# main.net
KiCad netlist of a schematic drawn in Altium Designer
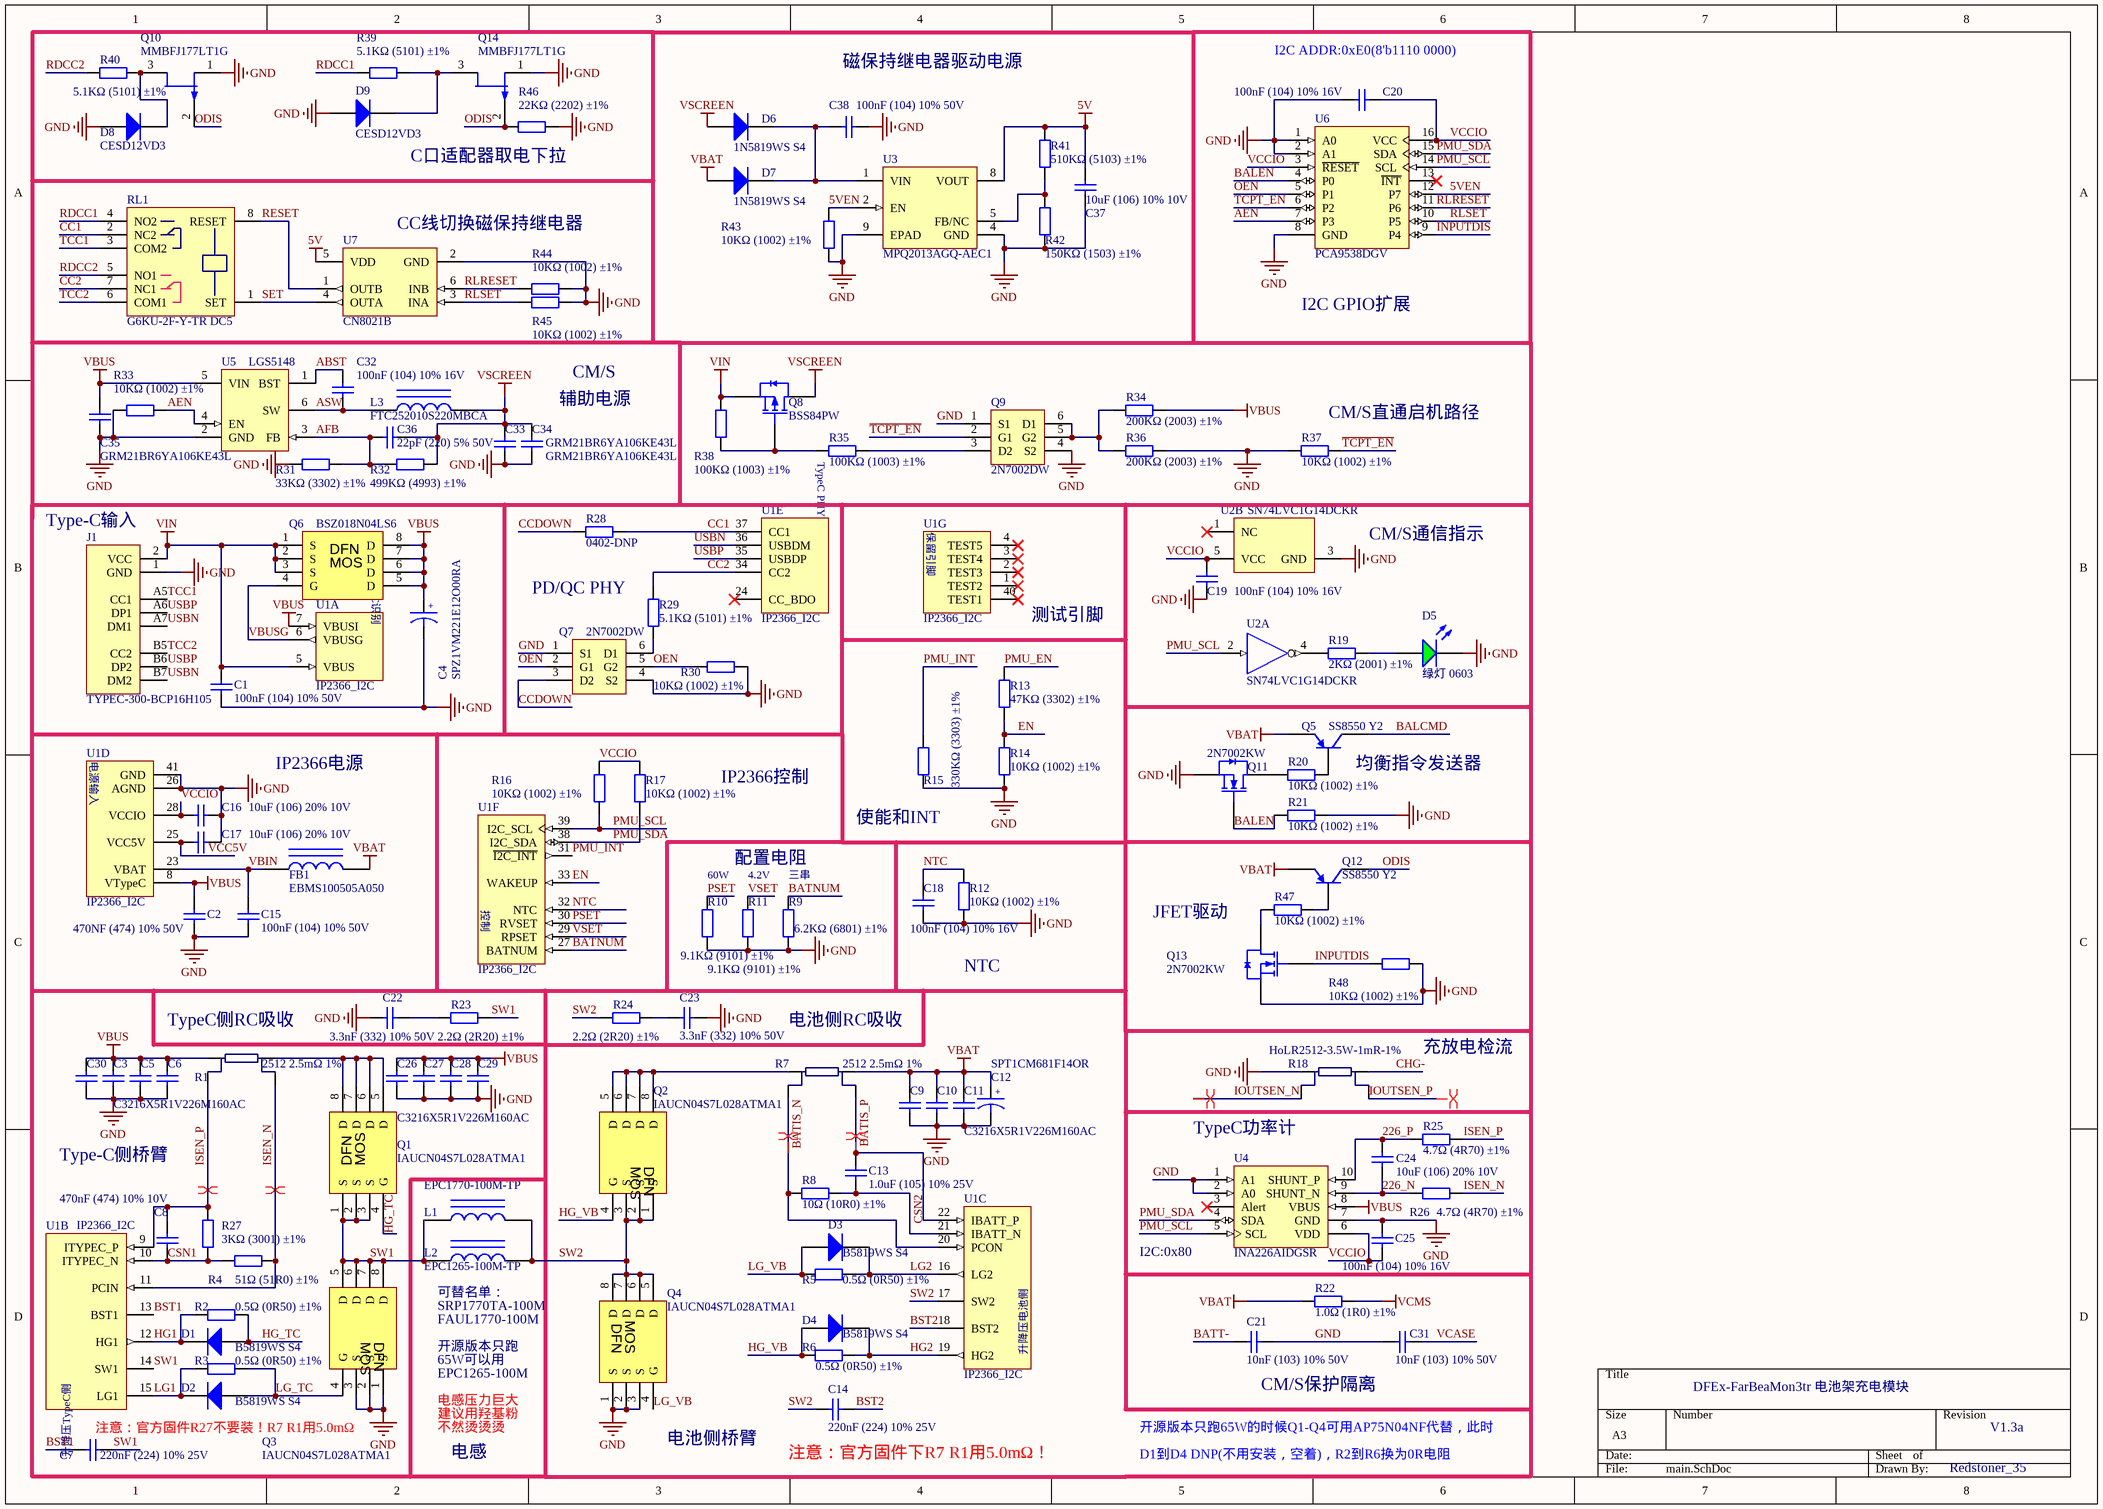
[diagram p0: main.SchDoc]

(export (version "E")
  (design (tool "Eeschema 10.0.6"))
  (components
    (comp (ref "C1")
      (value "100nF (104) 10% 50V")
      (footprint "0402_C")
      (description "贴片电容")
      (libsource (lib "Miscellaneous Devices LC") (part "0402 100nF (104) 10% 16V"))
    )
    (comp (ref "C2")
      (value "470NF (474) 10% 50V")
      (footprint "0402_C")
      (description "贴片电容")
      (libsource (lib "Miscellaneous Devices LC") (part "0402 1.0uF (105) 10% 25V"))
    )
    (comp (ref "C3")
      (value "C3216X5R1V226M160AC")
      (footprint "1206C")
      (description "1206尺寸TDK MLCC 35V 22uF")
      (fields (field (name "PUBLISHER") "Altium Limited"))
      (libsource (lib "山猫的集成库20190318") (part "Cap"))
    )
    (comp (ref "C4")
      (value "SPZ1VM221E12O00RA")
      (footprint "ElecCap_Hori")
      (description "直插固态电容，耐压35V容量220uF，尺寸6x11")
      (libsource (lib "山猫的集成库20190318") (part "CAP2"))
    )
    (comp (ref "C5")
      (value "C3216X5R1V226M160AC")
      (footprint "1206C")
      (description "1206尺寸TDK MLCC 35V 22uF")
      (fields (field (name "PUBLISHER") "Altium Limited"))
      (libsource (lib "山猫的集成库20190318") (part "Cap"))
    )
    (comp (ref "C6")
      (value "C3216X5R1V226M160AC")
      (footprint "1206C")
      (description "1206尺寸TDK MLCC 35V 22uF")
      (fields (field (name "PUBLISHER") "Altium Limited"))
      (libsource (lib "山猫的集成库20190318") (part "Cap"))
    )
    (comp (ref "C7")
      (value "220nF (224) 10% 25V")
      (footprint "0603_C")
      (description "贴片电容")
      (libsource (lib "Miscellaneous Devices LC") (part "0603 220nF (224) 10% 25V"))
    )
    (comp (ref "C8")
      (value "470nF (474) 10% 10V")
      (footprint "0402_C")
      (description "贴片电容")
      (libsource (lib "Miscellaneous Devices LC") (part "0402 470nF (474) 10% 10V"))
    )
    (comp (ref "C9")
      (value "C3216X5R1V226M160AC")
      (footprint "1206C")
      (description "1206尺寸TDK MLCC 35V 22uF")
      (fields (field (name "PUBLISHER") "Altium Limited"))
      (libsource (lib "山猫的集成库20190318") (part "Cap"))
    )
    (comp (ref "C10")
      (value "C3216X5R1V226M160AC")
      (footprint "1206C")
      (description "1206尺寸TDK MLCC 35V 22uF")
      (fields (field (name "PUBLISHER") "Altium Limited"))
      (libsource (lib "山猫的集成库20190318") (part "Cap"))
    )
    (comp (ref "C11")
      (value "C3216X5R1V226M160AC")
      (footprint "1206C")
      (description "1206尺寸TDK MLCC 35V 22uF")
      (fields (field (name "PUBLISHER") "Altium Limited"))
      (libsource (lib "山猫的集成库20190318") (part "Cap"))
    )
    (comp (ref "C12")
      (value "SPT1CM681F14OR")
      (footprint "ElecCap_Hori")
      (description "直插固态电容，耐压16V容量680uF，尺寸6x11")
      (libsource (lib "山猫的集成库20190318") (part "CAP2"))
    )
    (comp (ref "C13")
      (value "1.0uF (105) 10% 25V")
      (footprint "0402_C")
      (description "贴片电容")
      (libsource (lib "Miscellaneous Devices LC") (part "0402 1.0uF (105) 10% 25V"))
    )
    (comp (ref "C14")
      (value "220nF (224) 10% 25V")
      (footprint "0603_C")
      (description "贴片电容")
      (libsource (lib "Miscellaneous Devices LC") (part "0603 220nF (224) 10% 25V"))
    )
    (comp (ref "C15")
      (value "100nF (104) 10% 50V")
      (footprint "0402_C")
      (description "贴片电容")
      (libsource (lib "Miscellaneous Devices LC") (part "0402 100nF (104) 10% 16V"))
    )
    (comp (ref "C16")
      (value "10uF (106) 20% 10V")
      (footprint "0402_C")
      (description "贴片电容")
      (libsource (lib "Miscellaneous Devices LC") (part "0402 10uF (106) 20% 6.3V"))
    )
    (comp (ref "C17")
      (value "10uF (106) 20% 10V")
      (footprint "0402_C")
      (description "贴片电容")
      (libsource (lib "Miscellaneous Devices LC") (part "0402 10uF (106) 20% 6.3V"))
    )
    (comp (ref "C18")
      (value "100nF (104) 10% 16V")
      (footprint "0402_C")
      (description "贴片电容")
      (libsource (lib "Miscellaneous Devices LC") (part "0402 100nF (104) 10% 16V"))
    )
    (comp (ref "C19")
      (value "100nF (104) 10% 16V")
      (footprint "0402_C")
      (description "贴片电容")
      (libsource (lib "Miscellaneous Devices LC") (part "0402 100nF (104) 10% 16V"))
    )
    (comp (ref "C20")
      (value "100nF (104) 10% 16V")
      (footprint "0402_C")
      (description "贴片电容")
      (libsource (lib "Miscellaneous Devices LC") (part "0402 100nF (104) 10% 16V"))
    )
    (comp (ref "C21")
      (value "10nF (103) 10% 50V")
      (footprint "0402_C")
      (description "贴片电容")
      (libsource (lib "Miscellaneous Devices LC") (part "0402 10nF (103) 10% 50V"))
    )
    (comp (ref "C22")
      (value "3.3nF (332) 10% 50V")
      (footprint "0603_C")
      (description "贴片电容")
      (libsource (lib "Miscellaneous Devices LC") (part "0603 3.3nF (332) 10% 50V"))
    )
    (comp (ref "C23")
      (value "3.3nF (332) 10% 50V")
      (footprint "0603_C")
      (description "贴片电容")
      (libsource (lib "Miscellaneous Devices LC") (part "0603 3.3nF (332) 10% 50V"))
    )
    (comp (ref "C24")
      (value "10uF (106) 20% 10V")
      (footprint "0402_C")
      (description "贴片电容")
      (libsource (lib "Miscellaneous Devices LC") (part "0402 10uF (106) 20% 6.3V"))
    )
    (comp (ref "C25")
      (value "100nF (104) 10% 16V")
      (footprint "0402_C")
      (description "贴片电容")
      (libsource (lib "Miscellaneous Devices LC") (part "0402 100nF (104) 10% 16V"))
    )
    (comp (ref "C26")
      (value "C3216X5R1V226M160AC")
      (footprint "1206C")
      (description "1206尺寸TDK MLCC 35V 22uF")
      (fields (field (name "PUBLISHER") "Altium Limited"))
      (libsource (lib "山猫的集成库20190318") (part "Cap"))
    )
    (comp (ref "C27")
      (value "C3216X5R1V226M160AC")
      (footprint "1206C")
      (description "1206尺寸TDK MLCC 35V 22uF")
      (fields (field (name "PUBLISHER") "Altium Limited"))
      (libsource (lib "山猫的集成库20190318") (part "Cap"))
    )
    (comp (ref "C28")
      (value "C3216X5R1V226M160AC")
      (footprint "1206C")
      (description "1206尺寸TDK MLCC 35V 22uF")
      (fields (field (name "PUBLISHER") "Altium Limited"))
      (libsource (lib "山猫的集成库20190318") (part "Cap"))
    )
    (comp (ref "C29")
      (value "C3216X5R1V226M160AC")
      (footprint "1206C")
      (description "1206尺寸TDK MLCC 35V 22uF")
      (fields (field (name "PUBLISHER") "Altium Limited"))
      (libsource (lib "山猫的集成库20190318") (part "Cap"))
    )
    (comp (ref "C30")
      (value "C3216X5R1V226M160AC")
      (footprint "1206C")
      (description "1206尺寸TDK MLCC 35V 22uF")
      (fields (field (name "PUBLISHER") "Altium Limited"))
      (libsource (lib "山猫的集成库20190318") (part "Cap"))
    )
    (comp (ref "C31")
      (value "10nF (103) 10% 50V")
      (footprint "0402_C")
      (description "贴片电容")
      (libsource (lib "Miscellaneous Devices LC") (part "0402 10nF (103) 10% 50V"))
    )
    (comp (ref "C32")
      (value "100nF (104) 10% 16V")
      (footprint "0402_C")
      (description "贴片电容")
      (libsource (lib "Miscellaneous Devices LC") (part "0402 100nF (104) 10% 16V"))
    )
    (comp (ref "C33")
      (value "GRM21BR6YA106KE43L")
      (footprint "0805_C")
      (description "0805 10uF±10% 35V X5R贴片电容")
      (libsource (lib "Miscellaneous Devices LC") (part "0805 22uF (226) 20% 25V"))
    )
    (comp (ref "C34")
      (value "GRM21BR6YA106KE43L")
      (footprint "0805_C")
      (description "0805 10uF±10% 35V X5R贴片电容")
      (libsource (lib "Miscellaneous Devices LC") (part "0805 22uF (226) 20% 25V"))
    )
    (comp (ref "C35")
      (value "GRM21BR6YA106KE43L")
      (footprint "0805_C")
      (description "0805 10uF±10% 35V X5R贴片电容")
      (libsource (lib "Miscellaneous Devices LC") (part "0805 4.7uF (475) 10% 25V"))
    )
    (comp (ref "C36")
      (value "22pF (220) 5% 50V")
      (footprint "0402_C")
      (description "贴片电容")
      (libsource (lib "Miscellaneous Devices LC") (part "0402 22pF (220) 5% 50V"))
    )
    (comp (ref "C37")
      (value "10uF (106) 10% 10V")
      (footprint "0603_C")
      (description "贴片电容")
      (libsource (lib "Miscellaneous Devices LC") (part "0603 10uF (106) 10% 10V"))
    )
    (comp (ref "C38")
      (value "100nF (104) 10% 50V")
      (footprint "0402_C")
      (description "贴片电容")
      (libsource (lib "Miscellaneous Devices LC") (part "0402 100nF (104) 10% 16V"))
    )
    (comp (ref "D1")
      (value "B5819WS S4")
      (footprint "SOD-323")
      (description "二极管")
      (libsource (lib "Miscellaneous Devices LC") (part "SOD-323 1N4148WS T4"))
    )
    (comp (ref "D2")
      (value "B5819WS S4")
      (footprint "SOD-323")
      (description "二极管")
      (libsource (lib "Miscellaneous Devices LC") (part "SOD-323 1N4148WS T4"))
    )
    (comp (ref "D3")
      (value "B5819WS S4")
      (footprint "SOD-323")
      (description "二极管")
      (libsource (lib "Miscellaneous Devices LC") (part "SOD-323 1N4148WS T4"))
    )
    (comp (ref "D4")
      (value "B5819WS S4")
      (footprint "SOD-323")
      (description "二极管")
      (libsource (lib "Miscellaneous Devices LC") (part "SOD-323 1N4148WS T4"))
    )
    (comp (ref "D5")
      (value "绿灯 0603")
      (footprint "0603_LED_S1")
      (description "发光二极管")
      (libsource (lib "Miscellaneous Devices LC") (part "0603 绿灯"))
    )
    (comp (ref "D6")
      (value "1N5819WS S4")
      (footprint "SOD-323")
      (description "二极管")
      (libsource (lib "Miscellaneous Devices LC") (part "SOD-323 1N4148WS T4"))
    )
    (comp (ref "D7")
      (value "1N5819WS S4")
      (footprint "SOD-323")
      (description "二极管")
      (libsource (lib "Miscellaneous Devices LC") (part "SOD-323 1N4148WS T4"))
    )
    (comp (ref "D8")
      (value "CESD12VD3")
      (footprint "SOD-323")
      (description "TVS瞬态抑制二极管，12V击穿电压")
      (libsource (lib "Miscellaneous Devices LC") (part "SOD-323 1N4148WS T4"))
    )
    (comp (ref "D9")
      (value "CESD12VD3")
      (footprint "SOD-323")
      (description "TVS瞬态抑制二极管，12V击穿电压")
      (libsource (lib "Miscellaneous Devices LC") (part "SOD-323 1N4148WS T4"))
    )
    (comp (ref "FB1")
      (value "EBMS100505A050")
      (footprint "0402_L")
      (description "贴片磁珠 200mA 5R±25% 100MHz")
      (libsource (lib "Miscellaneous Devices LC") (part "0402 12nH  5%"))
    )
    (comp (ref "J1")
      (value "TYPEC-300-BCP16H105")
      (footprint "TYPE-C-SMD_TYPE-C16PIN")
      (description "立贴16Pin Type-C接口，总高度10.5mm")
      (libsource (lib "custom") (part "TYPEC-300-BCP16H105"))
    )
    (comp (ref "L1")
      (value "EPC1770-100M-TP")
      (footprint "IND1770-HD")
      (description "汇磁一体成型羟基粉电感，1770尺寸，10uH±20% 9.50mΩ DCR 25A饱和电流")
      (fields (field (name "PUBLISHER") "Altium Limited"))
      (libsource (lib "") (part "Inductor Iron_1"))
    )
    (comp (ref "L2")
      (value "EPC1265-100M-TP")
      (footprint "EPC1265-xxxM")
      (description "汇磁一体成型羟基粉电感，1265尺寸，10uH±20%")
      (fields (field (name "PUBLISHER") "Altium Limited"))
      (libsource (lib "") (part "Inductor Iron_1"))
    )
    (comp (ref "L3")
      (value "FTC252010S220MBCA")
      (footprint "SWPA252010S")
      (description "小型化一体成型T-CORE热压电感，22uH 2.5*2.0*1.0mm尺寸")
      (fields (field (name "PUBLISHER") "Altium Limited"))
      (libsource (lib "Miscellaneous Devices") (part "Inductor Iron"))
    )
    (comp (ref "Q1")
      (value "IAUCN04S7L028ATMA1")
      (footprint "SON/DFN5x6(MOS)")
      (description "40V, N-Ch, 2.80mΩ max, Automotive MOSFET, SSO8(5x6), OptiMOS™ 7")
      (libsource (lib "") (part "SON/DFN5x6 MOS_3"))
    )
    (comp (ref "Q2")
      (value "IAUCN04S7L028ATMA1")
      (footprint "SON/DFN5x6(MOS)")
      (description "40V, N-Ch, 2.80mΩ max, Automotive MOSFET, SSO8(5x6), OptiMOS™ 7")
      (libsource (lib "") (part "SON/DFN5x6 MOS_1"))
    )
    (comp (ref "Q3")
      (value "IAUCN04S7L028ATMA1")
      (footprint "SON/DFN5x6(MOS)")
      (description "40V, N-Ch, 2.80mΩ max, Automotive MOSFET, SSO8(5x6), OptiMOS™ 7")
      (libsource (lib "") (part "SON/DFN5x6 MOS_1"))
    )
    (comp (ref "Q4")
      (value "IAUCN04S7L028ATMA1")
      (footprint "SON/DFN5x6(MOS)")
      (description "40V, N-Ch, 2.80mΩ max, Automotive MOSFET, SSO8(5x6), OptiMOS™ 7")
      (libsource (lib "custom") (part "SON/DFN5x6 MOS"))
    )
    (comp (ref "Q5")
      (value "SS8550 Y2")
      (footprint "SOT-23(SOT-23-3)")
      (description "三极管")
      (libsource (lib "Miscellaneous Devices LC") (part "SOT-23 SS8550 Y2"))
    )
    (comp (ref "Q6")
      (value "BSZ018N04LS6")
      (footprint "DFN-8_L3.0-W3.0-P0.65-BL")
      (description "PDFN3x3 40V 60A 1.8mΩ N-Ch MOSFET")
      (libsource (lib "") (part "SON/DFN5x6 MOS_2"))
    )
    (comp (ref "Q7")
      (value "2N7002DW")
      (footprint "SC70-6")
      (description "Dual N-Channel MOSFET 60V340mA SOT-363")
      (libsource (lib "custom") (part "2N7002DW"))
    )
    (comp (ref "Q8")
      (value "BSS84PW")
      (footprint "SC70-3")
      (description "MOS(场效应管)")
      (libsource (lib "Miscellaneous Devices LC") (part "SI2301CDS-T1-GE3"))
    )
    (comp (ref "Q9")
      (value "2N7002DW")
      (footprint "SC70-6")
      (description "Dual N-Channel MOSFET 60V340mA SOT-363")
      (libsource (lib "custom") (part "2N7002DW"))
    )
    (comp (ref "Q10")
      (value "MMBFJ177LT1G")
      (footprint "SOT-23_N")
      (description "SOT-23-3耗尽型场效应管")
      (fields (field (name "PUBLISHER") "Altium Limited"))
      (libsource (lib "Miscellaneous Devices") (part "JFET-P"))
    )
    (comp (ref "Q11")
      (value "2N7002KW")
      (footprint "SC70-3")
      (description "单N沟道MOSFET(场效应管)")
      (libsource (lib "Miscellaneous Devices LC") (part "2N7002 7002"))
    )
    (comp (ref "Q12")
      (value "SS8550 Y2")
      (footprint "SC70-3")
      (description "PNP三极管，SOT-323 封装")
      (libsource (lib "Miscellaneous Devices LC") (part "SOT-23 SS8550 Y2"))
    )
    (comp (ref "Q13")
      (value "2N7002KW")
      (footprint "SC70-3")
      (description "单N沟道MOSFET(场效应管)")
      (libsource (lib "Miscellaneous Devices LC") (part "2N7002 7002"))
    )
    (comp (ref "Q14")
      (value "MMBFJ177LT1G")
      (footprint "SOT-23_N")
      (description "SOT-23-3耗尽型场效应管")
      (fields (field (name "PUBLISHER") "Altium Limited"))
      (libsource (lib "Miscellaneous Devices") (part "JFET-P"))
    )
    (comp (ref "R1")
      (value "2512 2.5mΩ 1%")
      (footprint "2512-Virtual4Wire")
      (description "2512尺寸高能电子束焊接合金检流电阻，2.5mΩ 3W 1%")
      (libsource (lib "custom") (part "shunt"))
    )
    (comp (ref "R2")
      (value "0.5Ω (0R50) ±1%")
      (footprint "0603_R")
      (description "贴片电阻")
      (libsource (lib "Miscellaneous Devices LC") (part "0603 0Ω (0R0) 1%"))
    )
    (comp (ref "R3")
      (value "0.5Ω (0R50) ±1%")
      (footprint "0603_R")
      (description "贴片电阻")
      (libsource (lib "Miscellaneous Devices LC") (part "0603 0Ω (0R0) 1%"))
    )
    (comp (ref "R4")
      (value "51Ω (51R0) ±1%")
      (footprint "0402_R")
      (description "贴片电阻")
      (libsource (lib "Miscellaneous Devices LC") (part "0402 51Ω (51R0) 1%"))
    )
    (comp (ref "R5")
      (value "0.5Ω (0R50) ±1%")
      (footprint "0603_R")
      (description "贴片电阻")
      (libsource (lib "Miscellaneous Devices LC") (part "0603 1.5KΩ (1501) 1%"))
    )
    (comp (ref "R6")
      (value "0.5Ω (0R50) ±1%")
      (footprint "0603_R")
      (description "贴片电阻")
      (libsource (lib "Miscellaneous Devices LC") (part "0603 1.5KΩ (1501) 1%"))
    )
    (comp (ref "R7")
      (value "2512 2.5mΩ 1%")
      (footprint "2512-Virtual4Wire")
      (description "2512尺寸高能电子束焊接合金检流电阻，2.5mΩ 3W 1%")
      (libsource (lib "custom") (part "shunt"))
    )
    (comp (ref "R8")
      (value "10Ω (10R0) ±1%")
      (footprint "0402_R")
      (description "贴片电阻")
      (libsource (lib "Miscellaneous Devices LC") (part "0402 10Ω (10R0) 1%"))
    )
    (comp (ref "R9")
      (value "6.2KΩ (6801) ±1%")
      (footprint "0402_R")
      (description "贴片电阻")
      (libsource (lib "Miscellaneous Devices LC") (part "0402 6.8KΩ (6801) 1%"))
    )
    (comp (ref "R10")
      (value "9.1KΩ (9101) ±1%")
      (footprint "0402_R")
      (description "贴片电阻")
      (libsource (lib "Miscellaneous Devices LC") (part "0402 6.8KΩ (6801) 1%"))
    )
    (comp (ref "R11")
      (value "9.1KΩ (9101) ±1%")
      (footprint "0402_R")
      (description "贴片电阻")
      (libsource (lib "Miscellaneous Devices LC") (part "0402 6.8KΩ (6801) 1%"))
    )
    (comp (ref "R12")
      (value "10KΩ (1002) ±1%")
      (footprint "0402_R")
      (description "贴片电阻")
      (libsource (lib "") (part "0402 10KΩ (1002) 1%_1"))
    )
    (comp (ref "R13")
      (value "47KΩ (3302) ±1%")
      (footprint "0603_R")
      (description "贴片电阻")
      (libsource (lib "Miscellaneous Devices LC") (part "0603 33KΩ (3302) 1%"))
    )
    (comp (ref "R14")
      (value "10KΩ (1002) ±1%")
      (footprint "0603_R")
      (description "贴片电阻")
      (libsource (lib "Miscellaneous Devices LC") (part "0603 10KΩ (1002) 1%"))
    )
    (comp (ref "R15")
      (value "330KΩ (3303) ±1%")
      (footprint "0603_R")
      (description "贴片电阻")
      (libsource (lib "Miscellaneous Devices LC") (part "0603 330KΩ (3303) 1%"))
    )
    (comp (ref "R16")
      (value "10KΩ (1002) ±1%")
      (footprint "0402_R")
      (description "贴片电阻")
      (libsource (lib "") (part "0402 10KΩ (1002) 1%_1"))
    )
    (comp (ref "R17")
      (value "10KΩ (1002) ±1%")
      (footprint "0402_R")
      (description "贴片电阻")
      (libsource (lib "") (part "0402 10KΩ (1002) 1%_1"))
    )
    (comp (ref "R18")
      (value "HoLR2512-3.5W-1mR-1%")
      (footprint "2512-Virtual4Wire")
      (description "2512尺寸低温飘合金检流电阻1.0mΩ 3.5W 1% TCR＜25PPM")
      (libsource (lib "custom") (part "shunt"))
    )
    (comp (ref "R19")
      (value "2KΩ (2001) ±1%")
      (footprint "0402_R")
      (description "贴片电阻")
      (libsource (lib "Miscellaneous Devices LC") (part "0402 2KΩ (2001) 1%"))
    )
    (comp (ref "R20")
      (value "10KΩ (1002) ±1%")
      (footprint "0402_R")
      (description "贴片电阻")
      (libsource (lib "Miscellaneous Devices LC") (part "0402 10KΩ (1002) 1%"))
    )
    (comp (ref "R21")
      (value "10KΩ (1002) ±1%")
      (footprint "0402_R")
      (description "贴片电阻")
      (libsource (lib "") (part "0402 10KΩ (1002) 1%_2"))
    )
    (comp (ref "R22")
      (value "1.0Ω (1R0) ±1%")
      (footprint "0805_R")
      (description "贴片电阻")
      (libsource (lib "Miscellaneous Devices LC") (part "0805 0Ω (0R0) 1%"))
    )
    (comp (ref "R23")
      (value "2.2Ω (2R20) ±1%")
      (footprint "0603_R")
      (description "贴片电阻")
      (libsource (lib "Miscellaneous Devices LC") (part "0603 2.2Ω (2R20) 1%"))
    )
    (comp (ref "R24")
      (value "2.2Ω (2R20) ±1%")
      (footprint "0603_R")
      (description "贴片电阻")
      (libsource (lib "") (part "0603 2.2Ω (2R20) 1%_1"))
    )
    (comp (ref "R25")
      (value "4.7Ω (4R70) ±1%")
      (footprint "0402_R")
      (description "贴片电阻")
      (libsource (lib "Miscellaneous Devices LC") (part "0402 4.7KΩ (4701) 1%"))
    )
    (comp (ref "R26")
      (value "4.7Ω (4R70) ±1%")
      (footprint "0402_R")
      (description "贴片电阻")
      (libsource (lib "Miscellaneous Devices LC") (part "0402 4.7KΩ (4701) 1%"))
    )
    (comp (ref "R27")
      (value "3KΩ (3001) ±1%")
      (footprint "0402_R")
      (description "贴片电阻")
      (libsource (lib "Miscellaneous Devices LC") (part "0402 3.3KΩ (3301) 1%"))
    )
    (comp (ref "R28")
      (value "0402-DNP")
      (footprint "0402_R")
      (description "测试焊点（特殊情况下焊贴片电阻）")
      (libsource (lib "") (part "0402 5.1KΩ (5101) 1%_1"))
    )
    (comp (ref "R29")
      (value "5.1KΩ (5101) ±1%")
      (footprint "0402_R")
      (description "贴片电阻")
      (libsource (lib "Miscellaneous Devices LC") (part "0402 5.1KΩ (5101) 1%"))
    )
    (comp (ref "R30")
      (value "10KΩ (1002) ±1%")
      (footprint "0402_R")
      (description "贴片电阻")
      (libsource (lib "Miscellaneous Devices LC") (part "0402 10KΩ (1002) 1%"))
    )
    (comp (ref "R31")
      (value "33KΩ (3302) ±1%")
      (footprint "0402_R")
      (description "贴片电阻")
      (libsource (lib "Miscellaneous Devices LC") (part "0402 300KΩ (3003) 1%"))
    )
    (comp (ref "R32")
      (value "499KΩ (4993) ±1%")
      (footprint "0402_R")
      (description "贴片电阻")
      (libsource (lib "") (part "0402 510KΩ (5103) 1%_1"))
    )
    (comp (ref "R33")
      (value "10KΩ (1002) ±1%")
      (footprint "0402_R")
      (description "贴片电阻")
      (libsource (lib "") (part "0402 10KΩ (1002) 1%_2"))
    )
    (comp (ref "R34")
      (value "200KΩ (2003) ±1%")
      (footprint "0402_R")
      (description "贴片电阻")
      (libsource (lib "Miscellaneous Devices LC") (part "0402 200KΩ (2003) 1%"))
    )
    (comp (ref "R35")
      (value "100KΩ (1003) ±1%")
      (footprint "0402_R")
      (description "贴片电阻")
      (libsource (lib "") (part "0402 100KΩ (1003) 1%_1"))
    )
    (comp (ref "R36")
      (value "200KΩ (2003) ±1%")
      (footprint "0402_R")
      (description "贴片电阻")
      (libsource (lib "Miscellaneous Devices LC") (part "0402 200KΩ (2003) 1%"))
    )
    (comp (ref "R37")
      (value "10KΩ (1002) ±1%")
      (footprint "0402_R")
      (description "贴片电阻")
      (libsource (lib "") (part "0402 10KΩ (1002) 1%_2"))
    )
    (comp (ref "R38")
      (value "100KΩ (1003) ±1%")
      (footprint "0402_R")
      (description "贴片电阻")
      (libsource (lib "Miscellaneous Devices LC") (part "0402 100KΩ (1003) 1%"))
    )
    (comp (ref "R39")
      (value "5.1KΩ (5101) ±1%")
      (footprint "0402_R")
      (description "贴片电阻")
      (libsource (lib "") (part "0402 5.1KΩ (5101) 1%_1"))
    )
    (comp (ref "R40")
      (value "5.1KΩ (5101) ±1%")
      (footprint "0402_R")
      (description "贴片电阻")
      (libsource (lib "") (part "0402 5.1KΩ (5101) 1%_1"))
    )
    (comp (ref "R41")
      (value "510KΩ (5103) ±1%")
      (footprint "0402_R")
      (description "贴片电阻")
      (libsource (lib "Miscellaneous Devices LC") (part "0402 510KΩ (5103) 1%"))
    )
    (comp (ref "R42")
      (value "150KΩ (1503) ±1%")
      (footprint "0402_R")
      (description "贴片电阻")
      (libsource (lib "Miscellaneous Devices LC") (part "0402 150KΩ (1503) 1%"))
    )
    (comp (ref "R43")
      (value "10KΩ (1002) ±1%")
      (footprint "0402_R")
      (description "贴片电阻")
      (libsource (lib "") (part "0402 10KΩ (1002) 1%_1"))
    )
    (comp (ref "R44")
      (value "10KΩ (1002) ±1%")
      (footprint "0402_R")
      (description "贴片电阻")
      (libsource (lib "") (part "0402 10KΩ (1002) 1%_2"))
    )
    (comp (ref "R45")
      (value "10KΩ (1002) ±1%")
      (footprint "0402_R")
      (description "贴片电阻")
      (libsource (lib "") (part "0402 10KΩ (1002) 1%_2"))
    )
    (comp (ref "R46")
      (value "22KΩ (2202) ±1%")
      (footprint "0402_R")
      (description "贴片电阻")
      (libsource (lib "Miscellaneous Devices LC") (part "0402 22KΩ (2202) 1%"))
    )
    (comp (ref "R47")
      (value "10KΩ (1002) ±1%")
      (footprint "0402_R")
      (description "贴片电阻")
      (libsource (lib "Miscellaneous Devices LC") (part "0402 10KΩ (1002) 1%"))
    )
    (comp (ref "R48")
      (value "10KΩ (1002) ±1%")
      (footprint "0402_R")
      (description "贴片电阻")
      (libsource (lib "Miscellaneous Devices LC") (part "0402 10KΩ (1002) 1%"))
    )
    (comp (ref "RL1")
      (value "G6KU-2F-Y-TR DC5")
      (footprint "RELAY-SMD_G6K-2F-Y")
      (description "欧姆龙双组触点磁保持贴片继电器")
      (libsource (lib "custom") (part "G6KU-2F-Y-TR DC5"))
    )
    (comp (ref "U1")
      (value "IP2366_I2C")
      (footprint "QFN40-IP2366")
      (description "支持多种快充协议，最高140W功率的充放电管理SoC")
      (libsource (lib "") (part "IP2366_I2C_1"))
    )
    (comp (ref "U2")
      (value "SN74LVC1G14DCKR")
      (footprint "DCK0005A_N")
      (description "Single Schmitt-Trigger Inverter, DCK0005A, LARGE T&R")
      (fields
        (field (name "GENERIC PART NUMBER") "SN74LVC1G14")
        (field (name "MANUFACTURER") "Texas Instruments")
      )
      (libsource (lib "TI_Logic_Little_Logic") (part "SN74LVC1G14DCKR"))
    )
    (comp (ref "U3")
      (value "MPQ2013AGQ-AEC1")
      (footprint "MPQ2013A-QFN8")
      (description "MPS 40V LDO with Enable pin QFN3x3 package")
      (libsource (lib "custom") (part "MPQ2013AGQ-xx-AEC1"))
    )
    (comp (ref "U4")
      (value "INA226AIDGSR")
      (footprint "MSOP-10")
      (description "具有警报功能的双向36V，16位，高精度I2C总线功率计")
      (libsource (lib "custom") (part "INA226AIDGSR"))
    )
    (comp (ref "U5")
      (value "LGS5148")
      (footprint "SOT95P245X110-6N")
      (description "48V输入，600mA同步降压转换器，SOT-23-6封装")
      (libsource (lib "custom") (part "LGS5148"))
    )
    (comp (ref "U6")
      (value "PCA9538DGV")
      (footprint "TVSOP-16_L3.6-W4.4-P0.40-LS6.4-BL")
      (description "具有中断输出、复位和配置寄存器的远程 8 位 I2C 和 SMBus 低功耗   I/O 扩展器")
      (libsource (lib "custom") (part "PCA9538DGV"))
    )
    (comp (ref "U7")
      (value "CN8021B")
      (footprint "SOT95P245X110-6N")
      (description "SOT23-6封装 双向磁保持继电器驱动IC 电压3.5-40V 450mA驱动能力")
      (libsource (lib "custom") (part "CN8023B"))
    )
  )
  (nets
    (net (code "1") (name "/5VEN") (class "Default")
      (node (ref "R43") (pin "2") (pinfunction "2_2") (pintype "passive"))
      (node (ref "U3") (pin "2") (pinfunction "EN_2") (pintype "input"))
      (node (ref "U6") (pin "12") (pinfunction "P7_12") (pintype "bidirectional"))
    )
    (net (code "2") (name "/226_N") (class "Default")
      (node (ref "C24") (pin "1") (pinfunction "1_1") (pintype "passive"))
      (node (ref "R26") (pin "1") (pinfunction "1_1") (pintype "passive"))
      (node (ref "U4") (pin "9") (pinfunction "SHUNT_N_9") (pintype "input"))
    )
    (net (code "3") (name "/226_P") (class "Default")
      (node (ref "C24") (pin "2") (pinfunction "2_2") (pintype "passive"))
      (node (ref "R25") (pin "1") (pinfunction "1_1") (pintype "passive"))
      (node (ref "U4") (pin "10") (pinfunction "SHUNT_P_10") (pintype "input"))
    )
    (net (code "4") (name "/ABST") (class "Default")
      (node (ref "C32") (pin "2") (pinfunction "2_2") (pintype "passive"))
      (node (ref "U5") (pin "1") (pinfunction "BST_1") (pintype "power_in"))
    )
    (net (code "5") (name "/AEN") (class "Default")
      (node (ref "R33") (pin "1") (pinfunction "1_1") (pintype "passive"))
      (node (ref "U5") (pin "4") (pinfunction "EN_4") (pintype "input"))
      (node (ref "U6") (pin "7") (pinfunction "P3_7") (pintype "bidirectional"))
    )
    (net (code "6") (name "/AFB") (class "Default")
      (node (ref "C36") (pin "1") (pinfunction "1_1") (pintype "passive"))
      (node (ref "R31") (pin "2") (pinfunction "2_2") (pintype "passive"))
      (node (ref "R32") (pin "1") (pinfunction "1_1") (pintype "passive"))
      (node (ref "U5") (pin "3") (pinfunction "FB_3") (pintype "input"))
    )
    (net (code "7") (name "/ASW") (class "Default")
      (node (ref "C32") (pin "1") (pinfunction "1_1") (pintype "passive"))
      (node (ref "L3") (pin "2") (pinfunction "2_2") (pintype "passive"))
      (node (ref "U5") (pin "6") (pinfunction "SW_6") (pintype "power_in"))
    )
    (net (code "8") (name "/BALCMD") (class "Default")
      (node (ref "Q5") (pin "3") (pinfunction "C_3") (pintype "passive"))
    )
    (net (code "9") (name "/BALEN") (class "Default")
      (node (ref "Q11") (pin "1") (pinfunction "G_1") (pintype "passive"))
      (node (ref "R21") (pin "2") (pinfunction "2_2") (pintype "passive"))
      (node (ref "U6") (pin "4") (pinfunction "P0_4") (pintype "bidirectional"))
    )
    (net (code "10") (name "/BATIS_N") (class "Default")
      (node (ref "R7") (pin "2") (pinfunction "CIN_2") (pintype "passive"))
      (node (ref "R8") (pin "1") (pinfunction "1_1") (pintype "passive"))
      (node (ref "U1") (pin "20") (pinfunction "PCON_20") (pintype "input"))
    )
    (net (code "11") (name "/BATIS_P") (class "Default")
      (node (ref "C13") (pin "2") (pinfunction "2_2") (pintype "passive"))
      (node (ref "R7") (pin "3") (pinfunction "CIN_3") (pintype "passive"))
      (node (ref "U1") (pin "22") (pinfunction "IBATT_P_22") (pintype "input"))
    )
    (net (code "12") (name "/BATNUM") (class "Default")
      (node (ref "R9") (pin "2") (pinfunction "2_2") (pintype "passive"))
      (node (ref "U1") (pin "27") (pinfunction "BATNUM_27") (pintype "input"))
    )
    (net (code "13") (name "/BATT-") (class "Default")
      (node (ref "C21") (pin "1") (pinfunction "1_1") (pintype "passive"))
    )
    (net (code "14") (name "/BST1") (class "Default")
      (node (ref "C7") (pin "1") (pinfunction "1_1") (pintype "passive"))
      (node (ref "U1") (pin "13") (pinfunction "BST1_13") (pintype "power_in"))
    )
    (net (code "15") (name "/BST2") (class "Default")
      (node (ref "C14") (pin "2") (pinfunction "2_2") (pintype "passive"))
      (node (ref "U1") (pin "18") (pinfunction "BST2_18") (pintype "power_in"))
    )
    (net (code "16") (name "/CC1") (class "Default")
      (node (ref "R28") (pin "2") (pinfunction "2_2") (pintype "passive"))
      (node (ref "RL1") (pin "2") (pinfunction "NC2_2") (pintype "passive"))
      (node (ref "U1") (pin "37") (pinfunction "CC1_37") (pintype "passive"))
    )
    (net (code "17") (name "/CC2") (class "Default")
      (node (ref "R29") (pin "2") (pinfunction "2_2") (pintype "passive"))
      (node (ref "RL1") (pin "7") (pinfunction "NC1_7") (pintype "passive"))
      (node (ref "U1") (pin "34") (pinfunction "CC2_34") (pintype "passive"))
    )
    (net (code "18") (name "/CCDOWN") (class "Default")
      (node (ref "Q7") (pin "3") (pinfunction "D2_3") (pintype "passive"))
      (node (ref "R28") (pin "1") (pinfunction "1_1") (pintype "passive"))
    )
    (net (code "19") (name "/CHG-") (class "Default")
      (node (ref "R18") (pin "0") (pinfunction "CIN_0") (pintype "passive"))
    )
    (net (code "20") (name "/CSN1") (class "Default")
      (node (ref "C8") (pin "1") (pinfunction "1_1") (pintype "passive"))
      (node (ref "R27") (pin "1") (pinfunction "1_1") (pintype "passive"))
      (node (ref "R4") (pin "1") (pinfunction "1_1") (pintype "passive"))
      (node (ref "U1") (pin "10") (pinfunction "ITYPEC_N_10") (pintype "input"))
    )
    (net (code "21") (name "/CSN2") (class "Default")
      (node (ref "C13") (pin "1") (pinfunction "1_1") (pintype "passive"))
      (node (ref "R8") (pin "2") (pinfunction "2_2") (pintype "passive"))
      (node (ref "U1") (pin "21") (pinfunction "IBATT_N_21") (pintype "input"))
    )
    (net (code "22") (name "/EN") (class "Default")
      (node (ref "R13") (pin "1") (pinfunction "1_1") (pintype "passive"))
      (node (ref "R14") (pin "2") (pinfunction "2_2") (pintype "passive"))
      (node (ref "U1") (pin "33") (pinfunction "WAKEUP_33") (pintype "input"))
    )
    (net (code "23") (name "/HG1") (class "Default")
      (node (ref "D1") (pin "2") (pinfunction "K_2") (pintype "passive"))
      (node (ref "R2") (pin "1") (pinfunction "1_1") (pintype "passive"))
      (node (ref "U1") (pin "12") (pinfunction "HG1_12") (pintype "output"))
    )
    (net (code "24") (name "/HG2") (class "Default")
      (node (ref "D4") (pin "2") (pinfunction "K_2") (pintype "passive"))
      (node (ref "R6") (pin "2") (pinfunction "2_2") (pintype "passive"))
      (node (ref "U1") (pin "19") (pinfunction "HG2_19") (pintype "output"))
    )
    (net (code "25") (name "/HG_TC") (class "Default")
      (node (ref "D1") (pin "1") (pinfunction "A_1") (pintype "passive"))
      (node (ref "Q1") (pin "4") (pinfunction "G_4") (pintype "passive"))
      (node (ref "R2") (pin "2") (pinfunction "2_2") (pintype "passive"))
    )
    (net (code "26") (name "/HG_VB") (class "Default")
      (node (ref "D4") (pin "1") (pinfunction "A_1") (pintype "passive"))
      (node (ref "Q2") (pin "4") (pinfunction "G_4") (pintype "passive"))
      (node (ref "R6") (pin "1") (pinfunction "1_1") (pintype "passive"))
    )
    (net (code "27") (name "/INPUTDIS") (class "Default")
      (node (ref "Q13") (pin "1") (pinfunction "G_1") (pintype "passive"))
      (node (ref "R48") (pin "1") (pinfunction "1_1") (pintype "passive"))
      (node (ref "U6") (pin "9") (pinfunction "P4_9") (pintype "bidirectional"))
    )
    (net (code "28") (name "/IOUTSEN_N") (class "Default")
      (node (ref "R18") (pin "3") (pinfunction "CIN_3") (pintype "passive"))
    )
    (net (code "29") (name "/IOUTSEN_P") (class "Default")
      (node (ref "R18") (pin "2") (pinfunction "CIN_2") (pintype "passive"))
    )
    (net (code "30") (name "/ISEN_N") (class "Default")
      (node (ref "R1") (pin "3") (pinfunction "CIN_3") (pintype "passive"))
      (node (ref "R26") (pin "2") (pinfunction "2_2") (pintype "passive"))
      (node (ref "R4") (pin "2") (pinfunction "2_2") (pintype "passive"))
      (node (ref "U1") (pin "11") (pinfunction "PCIN_11") (pintype "input"))
    )
    (net (code "31") (name "/ISEN_P") (class "Default")
      (node (ref "C8") (pin "2") (pinfunction "2_2") (pintype "passive"))
      (node (ref "R1") (pin "2") (pinfunction "CIN_2") (pintype "passive"))
      (node (ref "R25") (pin "2") (pinfunction "2_2") (pintype "passive"))
      (node (ref "R27") (pin "2") (pinfunction "2_2") (pintype "passive"))
      (node (ref "U1") (pin "9") (pinfunction "ITYPEC_P_9") (pintype "input"))
    )
    (net (code "32") (name "/LG1") (class "Default")
      (node (ref "D2") (pin "2") (pinfunction "K_2") (pintype "passive"))
      (node (ref "R3") (pin "1") (pinfunction "1_1") (pintype "passive"))
      (node (ref "U1") (pin "15") (pinfunction "LG1_15") (pintype "power_in"))
    )
    (net (code "33") (name "/LG2") (class "Default")
      (node (ref "D3") (pin "2") (pinfunction "K_2") (pintype "passive"))
      (node (ref "R5") (pin "2") (pinfunction "2_2") (pintype "passive"))
      (node (ref "U1") (pin "16") (pinfunction "LG2_16") (pintype "output"))
    )
    (net (code "34") (name "/LG_TC") (class "Default")
      (node (ref "D2") (pin "1") (pinfunction "A_1") (pintype "passive"))
      (node (ref "Q3") (pin "4") (pinfunction "G_4") (pintype "passive"))
      (node (ref "R3") (pin "2") (pinfunction "2_2") (pintype "passive"))
    )
    (net (code "35") (name "/LG_VB") (class "Default")
      (node (ref "D3") (pin "1") (pinfunction "A_1") (pintype "passive"))
      (node (ref "Q4") (pin "4") (pinfunction "G_4") (pintype "passive"))
      (node (ref "R5") (pin "1") (pinfunction "1_1") (pintype "passive"))
    )
    (net (code "36") (name "/NTC") (class "Default")
      (node (ref "C18") (pin "2") (pinfunction "2_2") (pintype "passive"))
      (node (ref "R12") (pin "2") (pinfunction "2_2") (pintype "passive"))
      (node (ref "U1") (pin "32") (pinfunction "NTC_32") (pintype "input"))
    )
    (net (code "37") (name "/ODIS") (class "Default")
      (node (ref "Q10") (pin "2") (pinfunction "G_2") (pintype "passive"))
      (node (ref "Q12") (pin "3") (pinfunction "C_3") (pintype "passive"))
      (node (ref "Q14") (pin "2") (pinfunction "G_2") (pintype "passive"))
      (node (ref "R46") (pin "1") (pinfunction "1_1") (pintype "passive"))
    )
    (net (code "38") (name "/OEN") (class "Default")
      (node (ref "Q7") (pin "2") (pinfunction "G1_2") (pintype "passive"))
      (node (ref "Q7") (pin "5") (pinfunction "G2_5") (pintype "passive"))
      (node (ref "R30") (pin "1") (pinfunction "1_1") (pintype "passive"))
      (node (ref "U6") (pin "5") (pinfunction "P1_5") (pintype "bidirectional"))
    )
    (net (code "39") (name "/PMU_EN") (class "Default")
      (node (ref "R13") (pin "2") (pinfunction "2_2") (pintype "passive"))
    )
    (net (code "40") (name "/PMU_INT") (class "Default")
      (node (ref "R15") (pin "2") (pinfunction "2_2") (pintype "passive"))
      (node (ref "U1") (pin "31") (pinfunction "~{I2C_INT}_31") (pintype "output"))
    )
    (net (code "41") (name "/PMU_SCL") (class "Default")
      (node (ref "R16") (pin "1") (pinfunction "1_1") (pintype "passive"))
      (node (ref "U1") (pin "39") (pinfunction "I2C_SCL_39") (pintype "input"))
      (node (ref "U2") (pin "2") (pinfunction "A_2") (pintype "input"))
      (node (ref "U4") (pin "5") (pinfunction "SCL_5") (pintype "input"))
      (node (ref "U6") (pin "14") (pinfunction "SCL_14") (pintype "input"))
    )
    (net (code "42") (name "/PMU_SDA") (class "Default")
      (node (ref "R17") (pin "1") (pinfunction "1_1") (pintype "passive"))
      (node (ref "U1") (pin "38") (pinfunction "I2C_SDA_38") (pintype "bidirectional"))
      (node (ref "U4") (pin "4") (pinfunction "SDA_4") (pintype "bidirectional"))
      (node (ref "U6") (pin "15") (pinfunction "SDA_15") (pintype "bidirectional"))
    )
    (net (code "43") (name "/PSET") (class "Default")
      (node (ref "R10") (pin "2") (pinfunction "2_2") (pintype "passive"))
      (node (ref "U1") (pin "30") (pinfunction "RVSET_30") (pintype "input"))
    )
    (net (code "44") (name "/RDCC1") (class "Default")
      (node (ref "R39") (pin "1") (pinfunction "1_1") (pintype "passive"))
      (node (ref "RL1") (pin "4") (pinfunction "NO2_4") (pintype "passive"))
    )
    (net (code "45") (name "/RDCC2") (class "Default")
      (node (ref "R40") (pin "1") (pinfunction "1_1") (pintype "passive"))
      (node (ref "RL1") (pin "5") (pinfunction "NO1_5") (pintype "passive"))
    )
    (net (code "46") (name "/RESET") (class "Default")
      (node (ref "RL1") (pin "8") (pinfunction "RESET_8") (pintype "passive"))
      (node (ref "U7") (pin "1") (pinfunction "OUTB_1") (pintype "output"))
    )
    (net (code "47") (name "/RLRESET") (class "Default")
      (node (ref "R44") (pin "2") (pinfunction "2_2") (pintype "passive"))
      (node (ref "U6") (pin "11") (pinfunction "P6_11") (pintype "bidirectional"))
      (node (ref "U7") (pin "6") (pinfunction "INB_6") (pintype "input"))
    )
    (net (code "48") (name "/RLSET") (class "Default")
      (node (ref "R45") (pin "2") (pinfunction "2_2") (pintype "passive"))
      (node (ref "U6") (pin "10") (pinfunction "P5_10") (pintype "bidirectional"))
      (node (ref "U7") (pin "3") (pinfunction "INA_3") (pintype "input"))
    )
    (net (code "49") (name "/SET") (class "Default")
      (node (ref "RL1") (pin "1") (pinfunction "SET_1") (pintype "passive"))
      (node (ref "U7") (pin "4") (pinfunction "OUTA_4") (pintype "output"))
    )
    (net (code "50") (name "/SW1") (class "Default")
      (node (ref "C7") (pin "2") (pinfunction "2_2") (pintype "passive"))
      (node (ref "L1") (pin "1") (pinfunction "1_1") (pintype "passive"))
      (node (ref "L2") (pin "1") (pinfunction "1_1") (pintype "passive"))
      (node (ref "Q1") (pin "1") (pinfunction "S_1") (pintype "passive"))
      (node (ref "Q1") (pin "2") (pinfunction "S_2") (pintype "passive"))
      (node (ref "Q1") (pin "3") (pinfunction "S_3") (pintype "passive"))
      (node (ref "Q3") (pin "5") (pinfunction "D_5") (pintype "passive"))
      (node (ref "Q3") (pin "6") (pinfunction "D_6") (pintype "passive"))
      (node (ref "Q3") (pin "7") (pinfunction "D_7") (pintype "passive"))
      (node (ref "Q3") (pin "8") (pinfunction "D_8") (pintype "passive"))
      (node (ref "R23") (pin "2") (pinfunction "2_2") (pintype "passive"))
      (node (ref "U1") (pin "14") (pinfunction "SW1_14") (pintype "power_in"))
    )
    (net (code "51") (name "/SW2") (class "Default")
      (node (ref "C14") (pin "1") (pinfunction "1_1") (pintype "passive"))
      (node (ref "L1") (pin "2") (pinfunction "2_2") (pintype "passive"))
      (node (ref "L2") (pin "2") (pinfunction "2_2") (pintype "passive"))
      (node (ref "Q2") (pin "1") (pinfunction "S_1") (pintype "passive"))
      (node (ref "Q2") (pin "2") (pinfunction "S_2") (pintype "passive"))
      (node (ref "Q2") (pin "3") (pinfunction "S_3") (pintype "passive"))
      (node (ref "Q4") (pin "5") (pinfunction "D_5") (pintype "passive"))
      (node (ref "Q4") (pin "6") (pinfunction "D_6") (pintype "passive"))
      (node (ref "Q4") (pin "7") (pinfunction "D_7") (pintype "passive"))
      (node (ref "Q4") (pin "8") (pinfunction "D_8") (pintype "passive"))
      (node (ref "R24") (pin "2") (pinfunction "2_2") (pintype "passive"))
      (node (ref "U1") (pin "17") (pinfunction "SW2_17") (pintype "power_in"))
    )
    (net (code "52") (name "/TCC1") (class "Default")
      (node (ref "J1") (pin "A5") (pinfunction "CC1_A5") (pintype "passive"))
      (node (ref "RL1") (pin "3") (pinfunction "COM2_3") (pintype "passive"))
    )
    (net (code "53") (name "/TCC2") (class "Default")
      (node (ref "J1") (pin "B5") (pinfunction "CC2_B5") (pintype "passive"))
      (node (ref "RL1") (pin "6") (pinfunction "COM1_6") (pintype "passive"))
    )
    (net (code "54") (name "/USBN") (class "Default")
      (node (ref "J1") (pin "A7") (pinfunction "DM1_A7") (pintype "passive"))
      (node (ref "J1") (pin "B7") (pinfunction "DM2_B7") (pintype "passive"))
      (node (ref "U1") (pin "36") (pinfunction "USBDM_36") (pintype "passive"))
    )
    (net (code "55") (name "/USBP") (class "Default")
      (node (ref "J1") (pin "A6") (pinfunction "DP1_A6") (pintype "passive"))
      (node (ref "J1") (pin "B6") (pinfunction "DP2_B6") (pintype "passive"))
      (node (ref "U1") (pin "35") (pinfunction "USBDP_35") (pintype "passive"))
    )
    (net (code "56") (name "/VBIN") (class "Default")
      (node (ref "C15") (pin "2") (pinfunction "2_2") (pintype "passive"))
      (node (ref "FB1") (pin "1") (pinfunction "1_1") (pintype "passive"))
      (node (ref "U1") (pin "23") (pinfunction "VBAT_23") (pintype "power_in"))
    )
    (net (code "57") (name "/VBUSG") (class "Default")
      (node (ref "Q6") (pin "4") (pinfunction "G_4") (pintype "passive"))
      (node (ref "U1") (pin "6") (pinfunction "VBUSG_6") (pintype "output"))
    )
    (net (code "58") (name "/VCASE") (class "Default")
      (node (ref "C31") (pin "2") (pinfunction "2_2") (pintype "passive"))
    )
    (net (code "59") (name "/VCC5V") (class "Default")
      (node (ref "C17") (pin "1") (pinfunction "1_1") (pintype "passive"))
      (node (ref "U1") (pin "25") (pinfunction "VCC5V_25") (pintype "power_in"))
    )
    (net (code "60") (name "/VCCIO") (class "Default")
      (node (ref "C16") (pin "1") (pinfunction "1_1") (pintype "passive"))
      (node (ref "C19") (pin "2") (pinfunction "2_2") (pintype "passive"))
      (node (ref "C20") (pin "2") (pinfunction "2_2") (pintype "passive"))
      (node (ref "C25") (pin "1") (pinfunction "1_1") (pintype "passive"))
      (node (ref "R16") (pin "2") (pinfunction "2_2") (pintype "passive"))
      (node (ref "R17") (pin "2") (pinfunction "2_2") (pintype "passive"))
      (node (ref "U1") (pin "28") (pinfunction "VCCIO_28") (pintype "power_in"))
      (node (ref "U2") (pin "5") (pinfunction "VCC_5") (pintype "power_in"))
      (node (ref "U4") (pin "6") (pinfunction "VDD_6") (pintype "power_in"))
      (node (ref "U6") (pin "16") (pinfunction "VCC_16") (pintype "power_in"))
      (node (ref "U6") (pin "3") (pinfunction "~{RESET}_3") (pintype "input"))
    )
    (net (code "61") (name "/VSET") (class "Default")
      (node (ref "R11") (pin "2") (pinfunction "2_2") (pintype "passive"))
      (node (ref "U1") (pin "29") (pinfunction "RPSET_29") (pintype "input"))
    )
    (net (code "62") (name "/~{TCPT_EN}") (class "Default")
      (node (ref "Q9") (pin "2") (pinfunction "G1_2") (pintype "passive"))
      (node (ref "R37") (pin "1") (pinfunction "1_1") (pintype "passive"))
      (node (ref "U6") (pin "6") (pinfunction "P2_6") (pintype "bidirectional"))
    )
    (net (code "63") (name "5V") (class "Default")
      (node (ref "C37") (pin "1") (pinfunction "1_1") (pintype "passive"))
      (node (ref "R41") (pin "2") (pinfunction "2_2") (pintype "passive"))
      (node (ref "U3") (pin "8") (pinfunction "VOUT_8") (pintype "passive"))
      (node (ref "U7") (pin "5") (pinfunction "VDD_5") (pintype "power_in"))
    )
    (net (code "64") (name "GND") (class "Default")
      (node (ref "C1") (pin "1") (pinfunction "1_1") (pintype "passive"))
      (node (ref "C10") (pin "1") (pinfunction "1_1") (pintype "passive"))
      (node (ref "C11") (pin "1") (pinfunction "1_1") (pintype "passive"))
      (node (ref "C12") (pin "2") (pinfunction "2_2") (pintype "passive"))
      (node (ref "C15") (pin "1") (pinfunction "1_1") (pintype "passive"))
      (node (ref "C16") (pin "2") (pinfunction "2_2") (pintype "passive"))
      (node (ref "C17") (pin "2") (pinfunction "2_2") (pintype "passive"))
      (node (ref "C18") (pin "1") (pinfunction "1_1") (pintype "passive"))
      (node (ref "C19") (pin "1") (pinfunction "1_1") (pintype "passive"))
      (node (ref "C2") (pin "1") (pinfunction "1_1") (pintype "passive"))
      (node (ref "C20") (pin "1") (pinfunction "1_1") (pintype "passive"))
      (node (ref "C21") (pin "2") (pinfunction "2_2") (pintype "passive"))
      (node (ref "C22") (pin "1") (pinfunction "1_1") (pintype "passive"))
      (node (ref "C23") (pin "1") (pinfunction "1_1") (pintype "passive"))
      (node (ref "C25") (pin "2") (pinfunction "2_2") (pintype "passive"))
      (node (ref "C26") (pin "1") (pinfunction "1_1") (pintype "passive"))
      (node (ref "C27") (pin "1") (pinfunction "1_1") (pintype "passive"))
      (node (ref "C28") (pin "1") (pinfunction "1_1") (pintype "passive"))
      (node (ref "C29") (pin "1") (pinfunction "1_1") (pintype "passive"))
      (node (ref "C3") (pin "1") (pinfunction "1_1") (pintype "passive"))
      (node (ref "C30") (pin "1") (pinfunction "1_1") (pintype "passive"))
      (node (ref "C31") (pin "1") (pinfunction "1_1") (pintype "passive"))
      (node (ref "C33") (pin "1") (pinfunction "1_1") (pintype "passive"))
      (node (ref "C34") (pin "1") (pinfunction "1_1") (pintype "passive"))
      (node (ref "C35") (pin "1") (pinfunction "1_1") (pintype "passive"))
      (node (ref "C37") (pin "2") (pinfunction "2_2") (pintype "passive"))
      (node (ref "C38") (pin "2") (pinfunction "2_2") (pintype "passive"))
      (node (ref "C4") (pin "2") (pinfunction "2_2") (pintype "passive"))
      (node (ref "C5") (pin "1") (pinfunction "1_1") (pintype "passive"))
      (node (ref "C6") (pin "1") (pinfunction "1_1") (pintype "passive"))
      (node (ref "C9") (pin "1") (pinfunction "1_1") (pintype "passive"))
      (node (ref "D5") (pin "K") (pinfunction "K_K") (pintype "passive"))
      (node (ref "D8") (pin "1") (pinfunction "A_1") (pintype "passive"))
      (node (ref "D9") (pin "1") (pinfunction "A_1") (pintype "passive"))
      (node (ref "J1") (pin "1") (pinfunction "GND_1") (pintype "passive"))
      (node (ref "Q10") (pin "1") (pinfunction "D_1") (pintype "passive"))
      (node (ref "Q11") (pin "2") (pinfunction "S_2") (pintype "passive"))
      (node (ref "Q13") (pin "2") (pinfunction "S_2") (pintype "passive"))
      (node (ref "Q14") (pin "1") (pinfunction "D_1") (pintype "passive"))
      (node (ref "Q3") (pin "1") (pinfunction "S_1") (pintype "passive"))
      (node (ref "Q3") (pin "2") (pinfunction "S_2") (pintype "passive"))
      (node (ref "Q3") (pin "3") (pinfunction "S_3") (pintype "passive"))
      (node (ref "Q4") (pin "1") (pinfunction "S_1") (pintype "passive"))
      (node (ref "Q4") (pin "2") (pinfunction "S_2") (pintype "passive"))
      (node (ref "Q4") (pin "3") (pinfunction "S_3") (pintype "passive"))
      (node (ref "Q7") (pin "1") (pinfunction "S1_1") (pintype "passive"))
      (node (ref "Q7") (pin "4") (pinfunction "S2_4") (pintype "passive"))
      (node (ref "Q9") (pin "1") (pinfunction "S1_1") (pintype "passive"))
      (node (ref "Q9") (pin "4") (pinfunction "S2_4") (pintype "passive"))
      (node (ref "R10") (pin "1") (pinfunction "1_1") (pintype "passive"))
      (node (ref "R11") (pin "1") (pinfunction "1_1") (pintype "passive"))
      (node (ref "R12") (pin "1") (pinfunction "1_1") (pintype "passive"))
      (node (ref "R14") (pin "1") (pinfunction "1_1") (pintype "passive"))
      (node (ref "R15") (pin "1") (pinfunction "1_1") (pintype "passive"))
      (node (ref "R18") (pin "1") (pinfunction "CIN_1") (pintype "passive"))
      (node (ref "R21") (pin "1") (pinfunction "1_1") (pintype "passive"))
      (node (ref "R30") (pin "2") (pinfunction "2_2") (pintype "passive"))
      (node (ref "R31") (pin "1") (pinfunction "1_1") (pintype "passive"))
      (node (ref "R33") (pin "2") (pinfunction "2_2") (pintype "passive"))
      (node (ref "R36") (pin "2") (pinfunction "2_2") (pintype "passive"))
      (node (ref "R37") (pin "2") (pinfunction "2_2") (pintype "passive"))
      (node (ref "R42") (pin "1") (pinfunction "1_1") (pintype "passive"))
      (node (ref "R43") (pin "1") (pinfunction "1_1") (pintype "passive"))
      (node (ref "R44") (pin "1") (pinfunction "1_1") (pintype "passive"))
      (node (ref "R45") (pin "1") (pinfunction "1_1") (pintype "passive"))
      (node (ref "R46") (pin "2") (pinfunction "2_2") (pintype "passive"))
      (node (ref "R48") (pin "2") (pinfunction "2_2") (pintype "passive"))
      (node (ref "R9") (pin "1") (pinfunction "1_1") (pintype "passive"))
      (node (ref "U1") (pin "26") (pinfunction "AGND_26") (pintype "power_in"))
      (node (ref "U1") (pin "41") (pinfunction "GND_41") (pintype "power_in"))
      (node (ref "U2") (pin "3") (pinfunction "GND_3") (pintype "power_in"))
      (node (ref "U3") (pin "4") (pinfunction "GND_4") (pintype "power_in"))
      (node (ref "U3") (pin "9") (pinfunction "EPAD_9") (pintype "passive"))
      (node (ref "U4") (pin "1") (pinfunction "A1_1") (pintype "input"))
      (node (ref "U4") (pin "2") (pinfunction "A0_2") (pintype "input"))
      (node (ref "U4") (pin "7") (pinfunction "GND_7") (pintype "power_in"))
      (node (ref "U5") (pin "2") (pinfunction "GND_2") (pintype "power_in"))
      (node (ref "U6") (pin "1") (pinfunction "A0_1") (pintype "input"))
      (node (ref "U6") (pin "2") (pinfunction "A1_2") (pintype "input"))
      (node (ref "U6") (pin "8") (pinfunction "GND_8") (pintype "power_in"))
      (node (ref "U7") (pin "2") (pinfunction "GND_2") (pintype "power_in"))
    )
    (net (code "65") (name "Net-(C22-Pad2)") (class "Default")
      (node (ref "C22") (pin "2") (pinfunction "2_2") (pintype "passive"))
      (node (ref "R23") (pin "1") (pinfunction "1_1") (pintype "passive"))
    )
    (net (code "66") (name "Net-(C23-Pad2)") (class "Default")
      (node (ref "C23") (pin "2") (pinfunction "2_2") (pintype "passive"))
      (node (ref "R24") (pin "1") (pinfunction "1_1") (pintype "passive"))
    )
    (net (code "67") (name "Net-(D5-PadA)") (class "Default")
      (node (ref "D5") (pin "A") (pinfunction "A_A") (pintype "passive"))
      (node (ref "R19") (pin "2") (pinfunction "2_2") (pintype "passive"))
    )
    (net (code "68") (name "Net-(D6-K)") (class "Default")
      (node (ref "C38") (pin "1") (pinfunction "1_1") (pintype "passive"))
      (node (ref "D6") (pin "2") (pinfunction "K_2") (pintype "passive"))
      (node (ref "D7") (pin "2") (pinfunction "K_2") (pintype "passive"))
      (node (ref "U3") (pin "1") (pinfunction "VIN_1") (pintype "power_in"))
    )
    (net (code "69") (name "Net-(D8-K)") (class "Default")
      (node (ref "D8") (pin "2") (pinfunction "K_2") (pintype "passive"))
      (node (ref "Q10") (pin "3") (pinfunction "S_3") (pintype "passive"))
      (node (ref "R40") (pin "2") (pinfunction "2_2") (pintype "passive"))
    )
    (net (code "70") (name "Net-(D9-K)") (class "Default")
      (node (ref "D9") (pin "2") (pinfunction "K_2") (pintype "passive"))
      (node (ref "Q14") (pin "3") (pinfunction "S_3") (pintype "passive"))
      (node (ref "R39") (pin "2") (pinfunction "2_2") (pintype "passive"))
    )
    (net (code "71") (name "Net-(Q1-D-Pad5)") (class "Default")
      (node (ref "Q1") (pin "5") (pinfunction "D_5") (pintype "passive"))
      (node (ref "Q1") (pin "6") (pinfunction "D_6") (pintype "passive"))
      (node (ref "Q1") (pin "7") (pinfunction "D_7") (pintype "passive"))
      (node (ref "Q1") (pin "8") (pinfunction "D_8") (pintype "passive"))
      (node (ref "R1") (pin "1") (pinfunction "CIN_1") (pintype "passive"))
    )
    (net (code "72") (name "Net-(Q2-D-Pad5)") (class "Default")
      (node (ref "Q2") (pin "5") (pinfunction "D_5") (pintype "passive"))
      (node (ref "Q2") (pin "6") (pinfunction "D_6") (pintype "passive"))
      (node (ref "Q2") (pin "7") (pinfunction "D_7") (pintype "passive"))
      (node (ref "Q2") (pin "8") (pinfunction "D_8") (pintype "passive"))
      (node (ref "R7") (pin "0") (pinfunction "CIN_0") (pintype "passive"))
    )
    (net (code "73") (name "Net-(Q5-B)") (class "Default")
      (node (ref "Q5") (pin "1") (pinfunction "B_1") (pintype "passive"))
      (node (ref "R20") (pin "2") (pinfunction "2_2") (pintype "passive"))
    )
    (net (code "74") (name "Net-(Q7-D1)") (class "Default")
      (node (ref "Q7") (pin "6") (pinfunction "D1_6") (pintype "passive"))
      (node (ref "R29") (pin "1") (pinfunction "1_1") (pintype "passive"))
    )
    (net (code "75") (name "Net-(Q8-G)") (class "Default")
      (node (ref "Q8") (pin "1") (pinfunction "G_1") (pintype "passive"))
      (node (ref "R35") (pin "2") (pinfunction "2_2") (pintype "passive"))
      (node (ref "R38") (pin "1") (pinfunction "1_1") (pintype "passive"))
    )
    (net (code "76") (name "Net-(Q9-D1)") (class "Default")
      (node (ref "Q9") (pin "5") (pinfunction "G2_5") (pintype "passive"))
      (node (ref "Q9") (pin "6") (pinfunction "D1_6") (pintype "passive"))
      (node (ref "R34") (pin "1") (pinfunction "1_1") (pintype "passive"))
      (node (ref "R36") (pin "1") (pinfunction "1_1") (pintype "passive"))
    )
    (net (code "77") (name "Net-(Q9-D2)") (class "Default")
      (node (ref "Q9") (pin "3") (pinfunction "D2_3") (pintype "passive"))
      (node (ref "R35") (pin "1") (pinfunction "1_1") (pintype "passive"))
    )
    (net (code "78") (name "Net-(Q11-D)") (class "Default")
      (node (ref "Q11") (pin "3") (pinfunction "D_3") (pintype "passive"))
      (node (ref "R20") (pin "1") (pinfunction "1_1") (pintype "passive"))
    )
    (net (code "79") (name "Net-(Q12-B)") (class "Default")
      (node (ref "Q12") (pin "1") (pinfunction "B_1") (pintype "passive"))
      (node (ref "R47") (pin "2") (pinfunction "2_2") (pintype "passive"))
    )
    (net (code "80") (name "Net-(Q13-D)") (class "Default")
      (node (ref "Q13") (pin "3") (pinfunction "D_3") (pintype "passive"))
      (node (ref "R47") (pin "1") (pinfunction "1_1") (pintype "passive"))
    )
    (net (code "81") (name "Net-(U2A-Y)") (class "Default")
      (node (ref "R19") (pin "1") (pinfunction "1_1") (pintype "passive"))
      (node (ref "U2") (pin "4") (pinfunction "Y_4") (pintype "output"))
    )
    (net (code "82") (name "Net-(U3-FB{slash}NC)") (class "Default")
      (node (ref "R41") (pin "1") (pinfunction "1_1") (pintype "passive"))
      (node (ref "R42") (pin "2") (pinfunction "2_2") (pintype "passive"))
      (node (ref "U3") (pin "5") (pinfunction "FB/NC_5") (pintype "passive"))
    )
    (net (code "83") (name "VBAT") (class "Default")
      (node (ref "C10") (pin "2") (pinfunction "2_2") (pintype "passive"))
      (node (ref "C11") (pin "2") (pinfunction "2_2") (pintype "passive"))
      (node (ref "C12") (pin "1") (pinfunction "1_1") (pintype "passive"))
      (node (ref "C9") (pin "2") (pinfunction "2_2") (pintype "passive"))
      (node (ref "D7") (pin "1") (pinfunction "A_1") (pintype "passive"))
      (node (ref "FB1") (pin "2") (pinfunction "2_2") (pintype "passive"))
      (node (ref "Q12") (pin "2") (pinfunction "E_2") (pintype "passive"))
      (node (ref "Q5") (pin "2") (pinfunction "E_2") (pintype "passive"))
      (node (ref "R22") (pin "1") (pinfunction "1_1") (pintype "passive"))
      (node (ref "R7") (pin "1") (pinfunction "CIN_1") (pintype "passive"))
    )
    (net (code "84") (name "VBUS") (class "Default")
      (node (ref "C2") (pin "2") (pinfunction "2_2") (pintype "passive"))
      (node (ref "C26") (pin "2") (pinfunction "2_2") (pintype "passive"))
      (node (ref "C27") (pin "2") (pinfunction "2_2") (pintype "passive"))
      (node (ref "C28") (pin "2") (pinfunction "2_2") (pintype "passive"))
      (node (ref "C29") (pin "2") (pinfunction "2_2") (pintype "passive"))
      (node (ref "C3") (pin "2") (pinfunction "2_2") (pintype "passive"))
      (node (ref "C30") (pin "2") (pinfunction "2_2") (pintype "passive"))
      (node (ref "C35") (pin "2") (pinfunction "2_2") (pintype "passive"))
      (node (ref "C4") (pin "1") (pinfunction "1_1") (pintype "passive"))
      (node (ref "C5") (pin "2") (pinfunction "2_2") (pintype "passive"))
      (node (ref "C6") (pin "2") (pinfunction "2_2") (pintype "passive"))
      (node (ref "Q6") (pin "5") (pinfunction "D_5") (pintype "passive"))
      (node (ref "Q6") (pin "6") (pinfunction "D_6") (pintype "passive"))
      (node (ref "Q6") (pin "7") (pinfunction "D_7") (pintype "passive"))
      (node (ref "Q6") (pin "8") (pinfunction "D_8") (pintype "passive"))
      (node (ref "R1") (pin "0") (pinfunction "CIN_0") (pintype "passive"))
      (node (ref "R34") (pin "2") (pinfunction "2_2") (pintype "passive"))
      (node (ref "U1") (pin "7") (pinfunction "VBUSI_7") (pintype "input"))
      (node (ref "U1") (pin "8") (pinfunction "VTypeC_8") (pintype "power_in"))
      (node (ref "U4") (pin "8") (pinfunction "VBUS_8") (pintype "input"))
      (node (ref "U5") (pin "5") (pinfunction "VIN_5") (pintype "power_in"))
    )
    (net (code "85") (name "VCMS") (class "Default")
      (node (ref "R22") (pin "2") (pinfunction "2_2") (pintype "passive"))
    )
    (net (code "86") (name "VIN") (class "Default")
      (node (ref "C1") (pin "2") (pinfunction "2_2") (pintype "passive"))
      (node (ref "J1") (pin "2") (pinfunction "VCC_2") (pintype "passive"))
      (node (ref "Q6") (pin "1") (pinfunction "S_1") (pintype "passive"))
      (node (ref "Q6") (pin "2") (pinfunction "S_2") (pintype "passive"))
      (node (ref "Q6") (pin "3") (pinfunction "S_3") (pintype "passive"))
      (node (ref "Q8") (pin "2") (pinfunction "S_2") (pintype "passive"))
      (node (ref "R38") (pin "2") (pinfunction "2_2") (pintype "passive"))
      (node (ref "U1") (pin "5") (pinfunction "VBUS_5") (pintype "input"))
    )
    (net (code "87") (name "VSCREEN") (class "Default")
      (node (ref "C33") (pin "2") (pinfunction "2_2") (pintype "passive"))
      (node (ref "C34") (pin "2") (pinfunction "2_2") (pintype "passive"))
      (node (ref "C36") (pin "2") (pinfunction "2_2") (pintype "passive"))
      (node (ref "D6") (pin "1") (pinfunction "A_1") (pintype "passive"))
      (node (ref "L3") (pin "1") (pinfunction "1_1") (pintype "passive"))
      (node (ref "Q8") (pin "3") (pinfunction "D_3") (pintype "passive"))
      (node (ref "R32") (pin "2") (pinfunction "2_2") (pintype "passive"))
    )
    (net (code "88") (name "unconnected-(U1E-CC_BDO-Pad24)") (class "Default")
      (node (ref "U1") (pin "24") (pinfunction "CC_BDO_24") (pintype "passive+no_connect"))
    )
    (net (code "89") (name "unconnected-(U1G-TEST1-Pad40)") (class "Default")
      (node (ref "U1") (pin "40") (pinfunction "TEST1_40") (pintype "passive+no_connect"))
    )
    (net (code "90") (name "unconnected-(U1G-TEST2-Pad1)") (class "Default")
      (node (ref "U1") (pin "1") (pinfunction "TEST2_1") (pintype "passive+no_connect"))
    )
    (net (code "91") (name "unconnected-(U1G-TEST3-Pad2)") (class "Default")
      (node (ref "U1") (pin "2") (pinfunction "TEST3_2") (pintype "passive+no_connect"))
    )
    (net (code "92") (name "unconnected-(U1G-TEST4-Pad3)") (class "Default")
      (node (ref "U1") (pin "3") (pinfunction "TEST4_3") (pintype "passive+no_connect"))
    )
    (net (code "93") (name "unconnected-(U1G-TEST5-Pad4)") (class "Default")
      (node (ref "U1") (pin "4") (pinfunction "TEST5_4") (pintype "passive+no_connect"))
    )
    (net (code "94") (name "unconnected-(U2B-NC-Pad1)") (class "Default")
      (node (ref "U2") (pin "1") (pinfunction "NC_1") (pintype "passive+no_connect"))
    )
    (net (code "95") (name "unconnected-(U4-Alert-Pad3)") (class "Default")
      (node (ref "U4") (pin "3") (pinfunction "Alert_3") (pintype "open_collector+no_connect"))
    )
    (net (code "96") (name "unconnected-(U6-~{INT}-Pad13)") (class "Default")
      (node (ref "U6") (pin "13") (pinfunction "~{INT}_13") (pintype "open_collector+no_connect"))
    )
  )
)
